# dababa.net
KiCad netlist of a schematic drawn in EAGLE
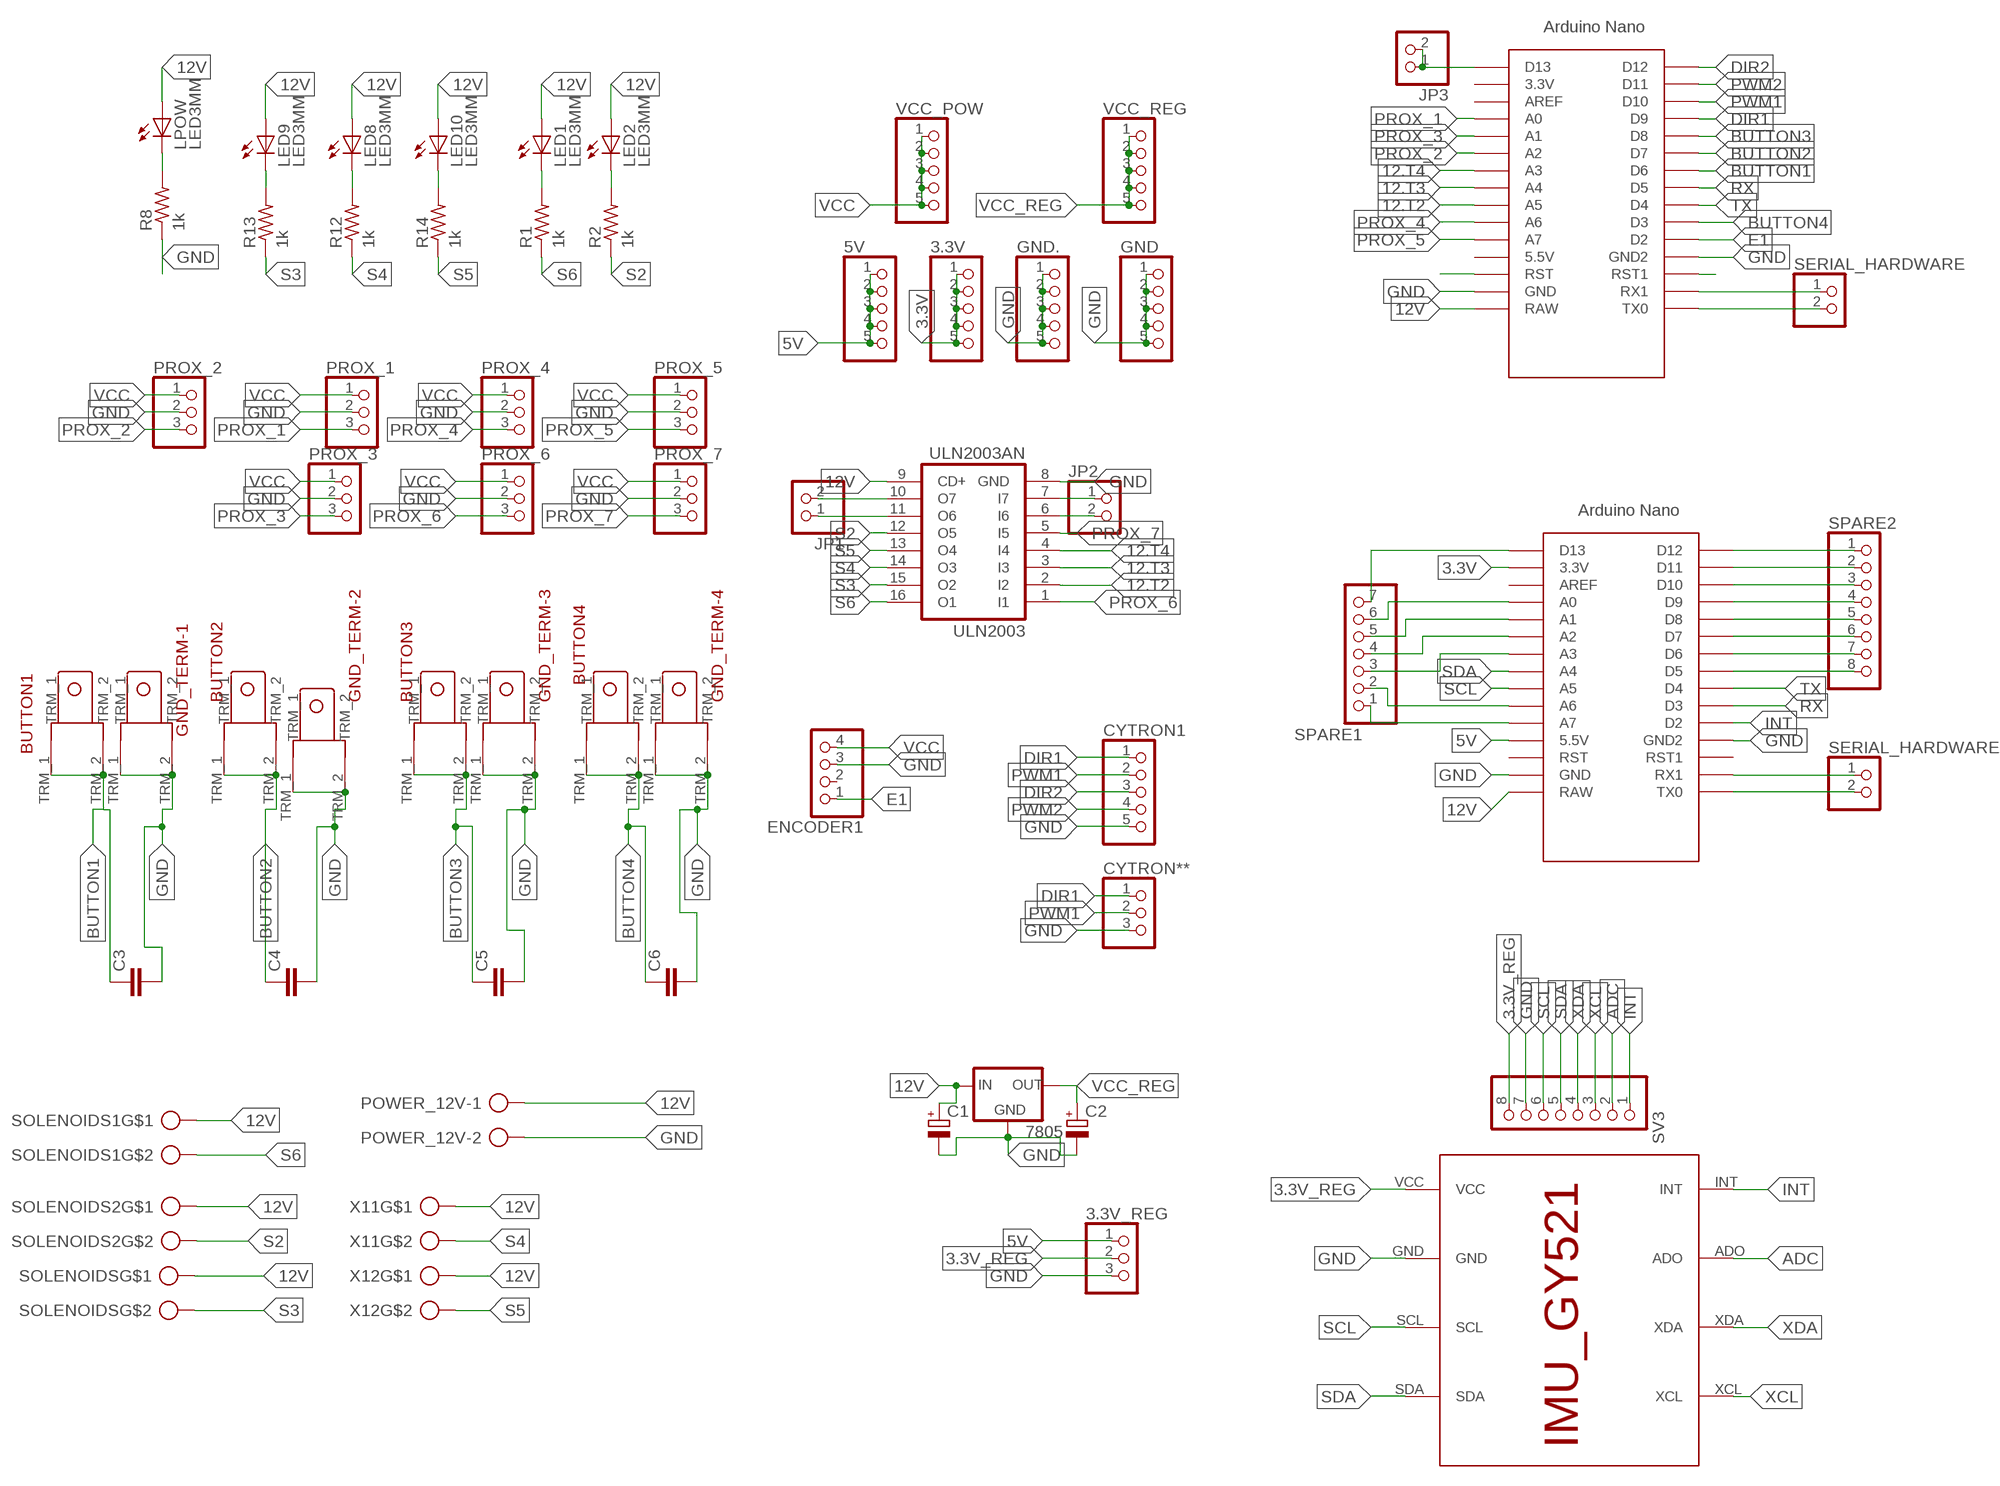
[diagram p0: schematic, sheet 1]

(export (version "E")
  (design (tool "Eeschema 10.0.6"))
  (components
    (comp (ref "3.3V")
      (value "PINHD-1X5")
      (footprint "eagle-import:1X05")
      (libsource (lib "eagle-import") (part "PINHD-1X5"))
    )
    (comp (ref "3.3V_REG")
      (value "PINHD-1X3")
      (footprint "eagle-import:1X03")
      (libsource (lib "eagle-import") (part "PINHD-1X3"))
    )
    (comp (ref "5V")
      (value "PINHD-1X5")
      (footprint "eagle-import:1X05")
      (libsource (lib "eagle-import") (part "PINHD-1X5"))
    )
    (comp (ref "7805")
      (value "78XXS")
      (footprint "eagle-import:78XXS")
      (libsource (lib "eagle-import") (part "78XXS"))
    )
    (comp (ref "BUTTON1")
      (value "TERMINAL_EDITED")
      (footprint "eagle-import:TERMINAL_EDITED")
      (libsource (lib "eagle-import") (part "TERMINAL_EDITED"))
    )
    (comp (ref "BUTTON2")
      (value "TERMINAL_EDITED")
      (footprint "eagle-import:TERMINAL_EDITED")
      (libsource (lib "eagle-import") (part "TERMINAL_EDITED"))
    )
    (comp (ref "BUTTON3")
      (value "TERMINAL_EDITED")
      (footprint "eagle-import:TERMINAL_EDITED")
      (libsource (lib "eagle-import") (part "TERMINAL_EDITED"))
    )
    (comp (ref "BUTTON4")
      (value "TERMINAL_EDITED")
      (footprint "eagle-import:TERMINAL_EDITED")
      (libsource (lib "eagle-import") (part "TERMINAL_EDITED"))
    )
    (comp (ref "C1")
      (value "CAP_POL")
      (footprint "eagle-import:E3,5-8")
      (libsource (lib "eagle-import") (part "CAP_POL"))
    )
    (comp (ref "C2")
      (value "CAP_POL")
      (footprint "eagle-import:E3,5-8")
      (libsource (lib "eagle-import") (part "CAP_POL"))
    )
    (comp (ref "C3")
      (value "CAPACITOR")
      (footprint "eagle-import:C025-025X050")
      (libsource (lib "eagle-import") (part "CAPACITOR"))
    )
    (comp (ref "C4")
      (value "CAPACITOR")
      (footprint "eagle-import:C025-025X050")
      (libsource (lib "eagle-import") (part "CAPACITOR"))
    )
    (comp (ref "C5")
      (value "CAPACITOR")
      (footprint "eagle-import:C025-025X050")
      (libsource (lib "eagle-import") (part "CAPACITOR"))
    )
    (comp (ref "C6")
      (value "CAPACITOR")
      (footprint "eagle-import:C025-025X050")
      (libsource (lib "eagle-import") (part "CAPACITOR"))
    )
    (comp (ref "CYTRON**")
      (value "PINHD-1X3")
      (footprint "eagle-import:1X03")
      (libsource (lib "eagle-import") (part "PINHD-1X3"))
    )
    (comp (ref "CYTRON1")
      (value "PINHD-1X5")
      (footprint "eagle-import:1X05")
      (libsource (lib "eagle-import") (part "PINHD-1X5"))
    )
    (comp (ref "ENCODER1")
      (value "PINHD-1X4")
      (footprint "eagle-import:1X04")
      (libsource (lib "eagle-import") (part "PINHD-1X4"))
    )
    (comp (ref "GND")
      (value "PINHD-1X5")
      (footprint "eagle-import:1X05")
      (libsource (lib "eagle-import") (part "PINHD-1X5"))
    )
    (comp (ref "GND.")
      (value "PINHD-1X5")
      (footprint "eagle-import:1X05")
      (libsource (lib "eagle-import") (part "PINHD-1X5"))
    )
    (comp (ref "GND_TERM-1")
      (value "TERMINAL_EDITED")
      (footprint "eagle-import:TERMINAL_EDITED")
      (libsource (lib "eagle-import") (part "TERMINAL_EDITED"))
    )
    (comp (ref "GND_TERM-2")
      (value "TERMINAL_EDITED")
      (footprint "eagle-import:TERMINAL_EDITED")
      (libsource (lib "eagle-import") (part "TERMINAL_EDITED"))
    )
    (comp (ref "GND_TERM-3")
      (value "TERMINAL_EDITED")
      (footprint "eagle-import:TERMINAL_EDITED")
      (libsource (lib "eagle-import") (part "TERMINAL_EDITED"))
    )
    (comp (ref "GND_TERM-4")
      (value "TERMINAL_EDITED")
      (footprint "eagle-import:TERMINAL_EDITED")
      (libsource (lib "eagle-import") (part "TERMINAL_EDITED"))
    )
    (comp (ref "JP1")
      (value "PINHD-1X2")
      (footprint "eagle-import:1X02")
      (libsource (lib "eagle-import") (part "PINHD-1X2"))
    )
    (comp (ref "JP2")
      (value "PINHD-1X2")
      (footprint "eagle-import:1X02")
      (libsource (lib "eagle-import") (part "PINHD-1X2"))
    )
    (comp (ref "JP3")
      (value "PINHD-1X2")
      (footprint "eagle-import:1X02")
      (libsource (lib "eagle-import") (part "PINHD-1X2"))
    )
    (comp (ref "LED1")
      (value "LED3MM")
      (footprint "eagle-import:LED3MM")
      (libsource (lib "eagle-import") (part "LED3MM"))
    )
    (comp (ref "LED2")
      (value "LED3MM")
      (footprint "eagle-import:LED3MM")
      (libsource (lib "eagle-import") (part "LED3MM"))
    )
    (comp (ref "LED8")
      (value "LED3MM")
      (footprint "eagle-import:LED3MM")
      (libsource (lib "eagle-import") (part "LED3MM"))
    )
    (comp (ref "LED9")
      (value "LED3MM")
      (footprint "eagle-import:LED3MM")
      (libsource (lib "eagle-import") (part "LED3MM"))
    )
    (comp (ref "LED10")
      (value "LED3MM")
      (footprint "eagle-import:LED3MM")
      (libsource (lib "eagle-import") (part "LED3MM"))
    )
    (comp (ref "LPOW")
      (value "LED3MM")
      (footprint "eagle-import:LED3MM")
      (libsource (lib "eagle-import") (part "LED3MM"))
    )
    (comp (ref "POWER_12V")
      (value "ROSTA.POWER")
      (footprint "eagle-import:W239-302")
      (libsource (lib "eagle-import") (part "ROSTA.POWER"))
    )
    (comp (ref "PROX_1")
      (value "PINHD-1X3")
      (footprint "eagle-import:1X03")
      (libsource (lib "eagle-import") (part "PINHD-1X3"))
    )
    (comp (ref "PROX_2")
      (value "PINHD-1X3")
      (footprint "eagle-import:1X03")
      (libsource (lib "eagle-import") (part "PINHD-1X3"))
    )
    (comp (ref "PROX_3")
      (value "PINHD-1X3")
      (footprint "eagle-import:1X03")
      (libsource (lib "eagle-import") (part "PINHD-1X3"))
    )
    (comp (ref "PROX_4")
      (value "PINHD-1X3")
      (footprint "eagle-import:1X03")
      (libsource (lib "eagle-import") (part "PINHD-1X3"))
    )
    (comp (ref "PROX_5")
      (value "PINHD-1X3")
      (footprint "eagle-import:1X03")
      (libsource (lib "eagle-import") (part "PINHD-1X3"))
    )
    (comp (ref "PROX_6")
      (value "PINHD-1X3")
      (footprint "eagle-import:1X03")
      (libsource (lib "eagle-import") (part "PINHD-1X3"))
    )
    (comp (ref "PROX_7")
      (value "PINHD-1X3")
      (footprint "eagle-import:1X03")
      (libsource (lib "eagle-import") (part "PINHD-1X3"))
    )
    (comp (ref "R1")
      (value "1k")
      (footprint "eagle-import:0204_5")
      (libsource (lib "eagle-import") (part "RES-5"))
    )
    (comp (ref "R2")
      (value "1k")
      (footprint "eagle-import:0204_5")
      (libsource (lib "eagle-import") (part "RES-5"))
    )
    (comp (ref "R8")
      (value "1k")
      (footprint "eagle-import:0204_5")
      (libsource (lib "eagle-import") (part "RES-5"))
    )
    (comp (ref "R12")
      (value "1k")
      (footprint "eagle-import:0204_5")
      (libsource (lib "eagle-import") (part "RES-5"))
    )
    (comp (ref "R13")
      (value "1k")
      (footprint "eagle-import:0204_5")
      (libsource (lib "eagle-import") (part "RES-5"))
    )
    (comp (ref "R14")
      (value "1k")
      (footprint "eagle-import:0204_5")
      (libsource (lib "eagle-import") (part "RES-5"))
    )
    (comp (ref "SERIAL_HARDWARE")
      (value "PINHD-1X2")
      (footprint "eagle-import:1X02")
      (libsource (lib "eagle-import") (part "PINHD-1X2"))
    )
    (comp (ref "SERIAL_HARDWARE1")
      (value "PINHD-1X2")
      (footprint "eagle-import:1X02")
      (libsource (lib "eagle-import") (part "PINHD-1X2"))
    )
    (comp (ref "SOLENOIDS")
      (value "CON_PTR_2")
      (footprint "eagle-import:AK300_2")
      (libsource (lib "eagle-import") (part "CON_PTR_2"))
    )
    (comp (ref "SOLENOIDS1")
      (value "CON_PTR_2")
      (footprint "eagle-import:AK300_2")
      (libsource (lib "eagle-import") (part "CON_PTR_2"))
    )
    (comp (ref "SOLENOIDS2")
      (value "CON_PTR_2")
      (footprint "eagle-import:AK300_2")
      (libsource (lib "eagle-import") (part "CON_PTR_2"))
    )
    (comp (ref "SPARE1")
      (value "PINHD-1X7")
      (footprint "eagle-import:1X07")
      (libsource (lib "eagle-import") (part "PINHD-1X7"))
    )
    (comp (ref "SPARE2")
      (value "PINHD-1X8")
      (footprint "eagle-import:1X08")
      (libsource (lib "eagle-import") (part "PINHD-1X8"))
    )
    (comp (ref "SV3")
      (value "PINHD-1X8")
      (footprint "eagle-import:1X08")
      (libsource (lib "eagle-import") (part "PINHD-1X8"))
    )
    (comp (ref "U$1")
      (value "ARDUINO_NANO")
      (footprint "eagle-import:NANO")
      (libsource (lib "eagle-import") (part "ARDUINO_NANO"))
    )
    (comp (ref "U$2")
      (value "IMU_ROBOCON_GY521")
      (footprint "eagle-import:IMU_GY521")
      (libsource (lib "eagle-import") (part "IMU_ROBOCON_GY521"))
    )
    (comp (ref "U$4")
      (value "ARDUINO_NANO")
      (footprint "eagle-import:NANO")
      (libsource (lib "eagle-import") (part "ARDUINO_NANO"))
    )
    (comp (ref "ULN2003")
      (value "ULN2003AN")
      (footprint "eagle-import:DIL16")
      (libsource (lib "eagle-import") (part "ULN2003AN"))
    )
    (comp (ref "VCC_POW")
      (value "PINHD-1X5")
      (footprint "eagle-import:1X05")
      (libsource (lib "eagle-import") (part "PINHD-1X5"))
    )
    (comp (ref "VCC_REG")
      (value "PINHD-1X5")
      (footprint "eagle-import:1X05")
      (libsource (lib "eagle-import") (part "PINHD-1X5"))
    )
    (comp (ref "X11")
      (value "CON_PTR_2")
      (footprint "eagle-import:AK300_2")
      (libsource (lib "eagle-import") (part "CON_PTR_2"))
    )
    (comp (ref "X12")
      (value "CON_PTR_2")
      (footprint "eagle-import:AK300_2")
      (libsource (lib "eagle-import") (part "CON_PTR_2"))
    )
  )
  (nets
    (net (code "1") (name "3.3V") (class "Default")
      (node (ref "3.3V") (pin "1") (pinfunction "1_1") (pintype "passive"))
      (node (ref "3.3V") (pin "2") (pinfunction "2_2") (pintype "passive"))
      (node (ref "3.3V") (pin "3") (pinfunction "3_3") (pintype "passive"))
      (node (ref "3.3V") (pin "4") (pinfunction "4_4") (pintype "passive"))
      (node (ref "3.3V") (pin "5") (pinfunction "5_5") (pintype "passive"))
      (node (ref "U$4") (pin "3.3V") (pinfunction "3.3V_3.3V") (pintype "bidirectional"))
    )
    (net (code "2") (name "3.3V_REG") (class "Default")
      (node (ref "3.3V_REG") (pin "2") (pinfunction "2_2") (pintype "passive"))
      (node (ref "SV3") (pin "8") (pinfunction "8_8") (pintype "passive"))
      (node (ref "U$2") (pin "VCC") (pinfunction "VCC_VCC") (pintype "bidirectional"))
    )
    (net (code "3") (name "5V") (class "Default")
      (node (ref "3.3V_REG") (pin "1") (pinfunction "1_1") (pintype "passive"))
      (node (ref "5V") (pin "1") (pinfunction "1_1") (pintype "passive"))
      (node (ref "5V") (pin "2") (pinfunction "2_2") (pintype "passive"))
      (node (ref "5V") (pin "3") (pinfunction "3_3") (pintype "passive"))
      (node (ref "5V") (pin "4") (pinfunction "4_4") (pintype "passive"))
      (node (ref "5V") (pin "5") (pinfunction "5_5") (pintype "passive"))
      (node (ref "U$4") (pin "5V") (pinfunction "5.5V_5V") (pintype "bidirectional"))
    )
    (net (code "4") (name "12.T2") (class "Default")
      (node (ref "U$1") (pin "A5") (pinfunction "A5_A5") (pintype "bidirectional"))
      (node (ref "ULN2003") (pin "2") (pinfunction "I2_2") (pintype "input"))
    )
    (net (code "5") (name "12.T3") (class "Default")
      (node (ref "U$1") (pin "A4") (pinfunction "A4_A4") (pintype "bidirectional"))
      (node (ref "ULN2003") (pin "3") (pinfunction "I3_3") (pintype "input"))
    )
    (net (code "6") (name "12.T4") (class "Default")
      (node (ref "U$1") (pin "A3") (pinfunction "A3_A3") (pintype "bidirectional"))
      (node (ref "ULN2003") (pin "4") (pinfunction "I4_4") (pintype "input"))
    )
    (net (code "7") (name "12V") (class "Default")
      (node (ref "7805") (pin "IN") (pinfunction "IN_IN") (pintype "input"))
      (node (ref "C1") (pin "+") (pinfunction "+_+") (pintype "passive"))
      (node (ref "LED1") (pin "A") (pinfunction "A_A") (pintype "passive"))
      (node (ref "LED10") (pin "A") (pinfunction "A_A") (pintype "passive"))
      (node (ref "LED2") (pin "A") (pinfunction "A_A") (pintype "passive"))
      (node (ref "LED8") (pin "A") (pinfunction "A_A") (pintype "passive"))
      (node (ref "LED9") (pin "A") (pinfunction "A_A") (pintype "passive"))
      (node (ref "LPOW") (pin "A") (pinfunction "A_A") (pintype "passive"))
      (node (ref "POWER_12V") (pin "1") (pinfunction "KL_1") (pintype "passive"))
      (node (ref "SOLENOIDS") (pin "1") (pinfunction "KL_1") (pintype "passive"))
      (node (ref "SOLENOIDS1") (pin "1") (pinfunction "KL_1") (pintype "passive"))
      (node (ref "SOLENOIDS2") (pin "1") (pinfunction "KL_1") (pintype "passive"))
      (node (ref "U$1") (pin "RAW") (pinfunction "RAW_RAW") (pintype "bidirectional"))
      (node (ref "U$4") (pin "RAW") (pinfunction "RAW_RAW") (pintype "bidirectional"))
      (node (ref "ULN2003") (pin "9") (pinfunction "CD+_9") (pintype "passive"))
      (node (ref "X11") (pin "1") (pinfunction "KL_1") (pintype "passive"))
      (node (ref "X12") (pin "1") (pinfunction "KL_1") (pintype "passive"))
    )
    (net (code "8") (name "ADC") (class "Default")
      (node (ref "SV3") (pin "2") (pinfunction "2_2") (pintype "passive"))
      (node (ref "U$2") (pin "ADO") (pinfunction "ADO_ADO") (pintype "bidirectional"))
    )
    (net (code "9") (name "BUTTON1") (class "Default")
      (node (ref "BUTTON1") (pin "TRM_1") (pinfunction "TRM_1_TRM_1") (pintype "bidirectional"))
      (node (ref "BUTTON1") (pin "TRM_2") (pinfunction "TRM_2_TRM_2") (pintype "bidirectional"))
      (node (ref "C3") (pin "1") (pinfunction "1_1") (pintype "passive"))
      (node (ref "U$1") (pin "D6") (pinfunction "D6_D6") (pintype "bidirectional"))
    )
    (net (code "10") (name "BUTTON2") (class "Default")
      (node (ref "BUTTON2") (pin "TRM_1") (pinfunction "TRM_1_TRM_1") (pintype "bidirectional"))
      (node (ref "BUTTON2") (pin "TRM_2") (pinfunction "TRM_2_TRM_2") (pintype "bidirectional"))
      (node (ref "C4") (pin "1") (pinfunction "1_1") (pintype "passive"))
      (node (ref "U$1") (pin "D7") (pinfunction "D7_D7") (pintype "bidirectional"))
    )
    (net (code "11") (name "BUTTON3") (class "Default")
      (node (ref "BUTTON3") (pin "TRM_1") (pinfunction "TRM_1_TRM_1") (pintype "bidirectional"))
      (node (ref "BUTTON3") (pin "TRM_2") (pinfunction "TRM_2_TRM_2") (pintype "bidirectional"))
      (node (ref "C5") (pin "1") (pinfunction "1_1") (pintype "passive"))
      (node (ref "U$1") (pin "D8") (pinfunction "D8_D8") (pintype "bidirectional"))
    )
    (net (code "12") (name "BUTTON4") (class "Default")
      (node (ref "BUTTON4") (pin "TRM_1") (pinfunction "TRM_1_TRM_1") (pintype "bidirectional"))
      (node (ref "BUTTON4") (pin "TRM_2") (pinfunction "TRM_2_TRM_2") (pintype "bidirectional"))
      (node (ref "C6") (pin "1") (pinfunction "1_1") (pintype "passive"))
      (node (ref "U$1") (pin "D3") (pinfunction "D3_D3") (pintype "bidirectional"))
    )
    (net (code "13") (name "DIR1") (class "Default")
      (node (ref "CYTRON**") (pin "1") (pinfunction "1_1") (pintype "passive"))
      (node (ref "CYTRON1") (pin "1") (pinfunction "1_1") (pintype "passive"))
      (node (ref "U$1") (pin "D9") (pinfunction "D9_D9") (pintype "bidirectional"))
    )
    (net (code "14") (name "DIR2") (class "Default")
      (node (ref "CYTRON1") (pin "3") (pinfunction "3_3") (pintype "passive"))
      (node (ref "U$1") (pin "D12") (pinfunction "D12_D12") (pintype "bidirectional"))
    )
    (net (code "15") (name "E1") (class "Default")
      (node (ref "ENCODER1") (pin "1") (pinfunction "1_1") (pintype "passive"))
      (node (ref "U$1") (pin "D2") (pinfunction "D2_D2") (pintype "bidirectional"))
    )
    (net (code "16") (name "GND") (class "Default")
      (node (ref "3.3V_REG") (pin "3") (pinfunction "3_3") (pintype "passive"))
      (node (ref "7805") (pin "GND") (pinfunction "GND_GND") (pintype "input"))
      (node (ref "C1") (pin "-") (pinfunction "-_-") (pintype "passive"))
      (node (ref "C2") (pin "-") (pinfunction "-_-") (pintype "passive"))
      (node (ref "C3") (pin "2") (pinfunction "2_2") (pintype "passive"))
      (node (ref "C4") (pin "2") (pinfunction "2_2") (pintype "passive"))
      (node (ref "C5") (pin "2") (pinfunction "2_2") (pintype "passive"))
      (node (ref "C6") (pin "2") (pinfunction "2_2") (pintype "passive"))
      (node (ref "CYTRON**") (pin "3") (pinfunction "3_3") (pintype "passive"))
      (node (ref "CYTRON1") (pin "5") (pinfunction "5_5") (pintype "passive"))
      (node (ref "ENCODER1") (pin "3") (pinfunction "3_3") (pintype "passive"))
      (node (ref "GND") (pin "1") (pinfunction "1_1") (pintype "passive"))
      (node (ref "GND") (pin "2") (pinfunction "2_2") (pintype "passive"))
      (node (ref "GND") (pin "3") (pinfunction "3_3") (pintype "passive"))
      (node (ref "GND") (pin "4") (pinfunction "4_4") (pintype "passive"))
      (node (ref "GND") (pin "5") (pinfunction "5_5") (pintype "passive"))
      (node (ref "GND.") (pin "1") (pinfunction "1_1") (pintype "passive"))
      (node (ref "GND.") (pin "2") (pinfunction "2_2") (pintype "passive"))
      (node (ref "GND.") (pin "3") (pinfunction "3_3") (pintype "passive"))
      (node (ref "GND.") (pin "4") (pinfunction "4_4") (pintype "passive"))
      (node (ref "GND.") (pin "5") (pinfunction "5_5") (pintype "passive"))
      (node (ref "GND_TERM-1") (pin "TRM_1") (pinfunction "TRM_1_TRM_1") (pintype "bidirectional"))
      (node (ref "GND_TERM-1") (pin "TRM_2") (pinfunction "TRM_2_TRM_2") (pintype "bidirectional"))
      (node (ref "GND_TERM-2") (pin "TRM_1") (pinfunction "TRM_1_TRM_1") (pintype "bidirectional"))
      (node (ref "GND_TERM-2") (pin "TRM_2") (pinfunction "TRM_2_TRM_2") (pintype "bidirectional"))
      (node (ref "GND_TERM-3") (pin "TRM_1") (pinfunction "TRM_1_TRM_1") (pintype "bidirectional"))
      (node (ref "GND_TERM-3") (pin "TRM_2") (pinfunction "TRM_2_TRM_2") (pintype "bidirectional"))
      (node (ref "GND_TERM-4") (pin "TRM_1") (pinfunction "TRM_1_TRM_1") (pintype "bidirectional"))
      (node (ref "GND_TERM-4") (pin "TRM_2") (pinfunction "TRM_2_TRM_2") (pintype "bidirectional"))
      (node (ref "POWER_12V") (pin "2") (pinfunction "KL_2") (pintype "passive"))
      (node (ref "PROX_1") (pin "2") (pinfunction "2_2") (pintype "passive"))
      (node (ref "PROX_2") (pin "2") (pinfunction "2_2") (pintype "passive"))
      (node (ref "PROX_3") (pin "2") (pinfunction "2_2") (pintype "passive"))
      (node (ref "PROX_4") (pin "2") (pinfunction "2_2") (pintype "passive"))
      (node (ref "PROX_5") (pin "2") (pinfunction "2_2") (pintype "passive"))
      (node (ref "PROX_6") (pin "2") (pinfunction "2_2") (pintype "passive"))
      (node (ref "PROX_7") (pin "2") (pinfunction "2_2") (pintype "passive"))
      (node (ref "R8") (pin "1") (pinfunction "1_1") (pintype "passive"))
      (node (ref "SV3") (pin "7") (pinfunction "7_7") (pintype "passive"))
      (node (ref "U$1") (pin "GND") (pinfunction "GND_GND") (pintype "bidirectional"))
      (node (ref "U$1") (pin "GND1") (pinfunction "GND2_GND1") (pintype "bidirectional"))
      (node (ref "U$2") (pin "GND") (pinfunction "GND_GND") (pintype "bidirectional"))
      (node (ref "U$4") (pin "GND") (pinfunction "GND_GND") (pintype "bidirectional"))
      (node (ref "U$4") (pin "GND1") (pinfunction "GND2_GND1") (pintype "bidirectional"))
      (node (ref "ULN2003") (pin "8") (pinfunction "GND_8") (pintype "power_in"))
    )
    (net (code "17") (name "INT") (class "Default")
      (node (ref "SV3") (pin "1") (pinfunction "1_1") (pintype "passive"))
      (node (ref "U$2") (pin "INT") (pinfunction "INT_INT") (pintype "bidirectional"))
      (node (ref "U$4") (pin "D2") (pinfunction "D2_D2") (pintype "bidirectional"))
    )
    (net (code "18") (name "Net-(JP3-Pad1)") (class "Default")
      (node (ref "JP3") (pin "1") (pinfunction "1_1") (pintype "passive"))
      (node (ref "JP3") (pin "2") (pinfunction "2_2") (pintype "passive"))
      (node (ref "U$1") (pin "D13") (pinfunction "D13_D13") (pintype "bidirectional"))
    )
    (net (code "19") (name "Net-(LED1-C)") (class "Default")
      (node (ref "LED1") (pin "K") (pinfunction "C_K") (pintype "passive"))
      (node (ref "R1") (pin "2") (pinfunction "2_2") (pintype "passive"))
    )
    (net (code "20") (name "Net-(LED2-C)") (class "Default")
      (node (ref "LED2") (pin "K") (pinfunction "C_K") (pintype "passive"))
      (node (ref "R2") (pin "2") (pinfunction "2_2") (pintype "passive"))
    )
    (net (code "21") (name "Net-(LED8-C)") (class "Default")
      (node (ref "LED8") (pin "K") (pinfunction "C_K") (pintype "passive"))
      (node (ref "R12") (pin "2") (pinfunction "2_2") (pintype "passive"))
    )
    (net (code "22") (name "Net-(LED9-C)") (class "Default")
      (node (ref "LED9") (pin "K") (pinfunction "C_K") (pintype "passive"))
      (node (ref "R13") (pin "2") (pinfunction "2_2") (pintype "passive"))
    )
    (net (code "23") (name "Net-(LED10-C)") (class "Default")
      (node (ref "LED10") (pin "K") (pinfunction "C_K") (pintype "passive"))
      (node (ref "R14") (pin "2") (pinfunction "2_2") (pintype "passive"))
    )
    (net (code "24") (name "Net-(LPOW-C)") (class "Default")
      (node (ref "LPOW") (pin "K") (pinfunction "C_K") (pintype "passive"))
      (node (ref "R8") (pin "2") (pinfunction "2_2") (pintype "passive"))
    )
    (net (code "25") (name "Net-(SERIAL_HARDWARE-Pad1)") (class "Default")
      (node (ref "SERIAL_HARDWARE") (pin "1") (pinfunction "1_1") (pintype "passive"))
      (node (ref "U$1") (pin "RX1") (pinfunction "RX1_RX1") (pintype "bidirectional"))
    )
    (net (code "26") (name "Net-(SERIAL_HARDWARE-Pad2)") (class "Default")
      (node (ref "SERIAL_HARDWARE") (pin "2") (pinfunction "2_2") (pintype "passive"))
      (node (ref "U$1") (pin "TX0") (pinfunction "TX0_TX0") (pintype "bidirectional"))
    )
    (net (code "27") (name "Net-(SERIAL_HARDWARE1-Pad1)") (class "Default")
      (node (ref "SERIAL_HARDWARE1") (pin "1") (pinfunction "1_1") (pintype "passive"))
      (node (ref "U$4") (pin "RX1") (pinfunction "RX1_RX1") (pintype "bidirectional"))
    )
    (net (code "28") (name "Net-(SERIAL_HARDWARE1-Pad2)") (class "Default")
      (node (ref "SERIAL_HARDWARE1") (pin "2") (pinfunction "2_2") (pintype "passive"))
      (node (ref "U$4") (pin "TX0") (pinfunction "TX0_TX0") (pintype "bidirectional"))
    )
    (net (code "29") (name "Net-(SPARE1-Pad1)") (class "Default")
      (node (ref "SPARE1") (pin "1") (pinfunction "1_1") (pintype "passive"))
      (node (ref "U$4") (pin "A7") (pinfunction "A7_A7") (pintype "bidirectional"))
    )
    (net (code "30") (name "Net-(SPARE1-Pad2)") (class "Default")
      (node (ref "SPARE1") (pin "2") (pinfunction "2_2") (pintype "passive"))
      (node (ref "U$4") (pin "A6") (pinfunction "A6_A6") (pintype "bidirectional"))
    )
    (net (code "31") (name "Net-(SPARE1-Pad3)") (class "Default")
      (node (ref "SPARE1") (pin "3") (pinfunction "3_3") (pintype "passive"))
      (node (ref "U$4") (pin "A3") (pinfunction "A3_A3") (pintype "bidirectional"))
    )
    (net (code "32") (name "Net-(SPARE1-Pad4)") (class "Default")
      (node (ref "SPARE1") (pin "4") (pinfunction "4_4") (pintype "passive"))
      (node (ref "U$4") (pin "A2") (pinfunction "A2_A2") (pintype "bidirectional"))
    )
    (net (code "33") (name "Net-(SPARE1-Pad5)") (class "Default")
      (node (ref "SPARE1") (pin "5") (pinfunction "5_5") (pintype "passive"))
      (node (ref "U$4") (pin "A1") (pinfunction "A1_A1") (pintype "bidirectional"))
    )
    (net (code "34") (name "Net-(SPARE1-Pad6)") (class "Default")
      (node (ref "SPARE1") (pin "6") (pinfunction "6_6") (pintype "passive"))
      (node (ref "U$4") (pin "A0") (pinfunction "A0_A0") (pintype "bidirectional"))
    )
    (net (code "35") (name "Net-(SPARE1-Pad7)") (class "Default")
      (node (ref "SPARE1") (pin "7") (pinfunction "7_7") (pintype "passive"))
      (node (ref "U$4") (pin "D13") (pinfunction "D13_D13") (pintype "bidirectional"))
    )
    (net (code "36") (name "Net-(SPARE2-Pad1)") (class "Default")
      (node (ref "SPARE2") (pin "1") (pinfunction "1_1") (pintype "passive"))
      (node (ref "U$4") (pin "D12") (pinfunction "D12_D12") (pintype "bidirectional"))
    )
    (net (code "37") (name "Net-(SPARE2-Pad2)") (class "Default")
      (node (ref "SPARE2") (pin "2") (pinfunction "2_2") (pintype "passive"))
      (node (ref "U$4") (pin "D11") (pinfunction "D11_D11") (pintype "bidirectional"))
    )
    (net (code "38") (name "Net-(SPARE2-Pad3)") (class "Default")
      (node (ref "SPARE2") (pin "3") (pinfunction "3_3") (pintype "passive"))
      (node (ref "U$4") (pin "D10") (pinfunction "D10_D10") (pintype "bidirectional"))
    )
    (net (code "39") (name "Net-(SPARE2-Pad4)") (class "Default")
      (node (ref "SPARE2") (pin "4") (pinfunction "4_4") (pintype "passive"))
      (node (ref "U$4") (pin "D9") (pinfunction "D9_D9") (pintype "bidirectional"))
    )
    (net (code "40") (name "Net-(SPARE2-Pad5)") (class "Default")
      (node (ref "SPARE2") (pin "5") (pinfunction "5_5") (pintype "passive"))
      (node (ref "U$4") (pin "D8") (pinfunction "D8_D8") (pintype "bidirectional"))
    )
    (net (code "41") (name "Net-(SPARE2-Pad6)") (class "Default")
      (node (ref "SPARE2") (pin "6") (pinfunction "6_6") (pintype "passive"))
      (node (ref "U$4") (pin "D7") (pinfunction "D7_D7") (pintype "bidirectional"))
    )
    (net (code "42") (name "Net-(SPARE2-Pad7)") (class "Default")
      (node (ref "SPARE2") (pin "7") (pinfunction "7_7") (pintype "passive"))
      (node (ref "U$4") (pin "D6") (pinfunction "D6_D6") (pintype "bidirectional"))
    )
    (net (code "43") (name "Net-(SPARE2-Pad8)") (class "Default")
      (node (ref "SPARE2") (pin "8") (pinfunction "8_8") (pintype "passive"))
      (node (ref "U$4") (pin "D5") (pinfunction "D5_D5") (pintype "bidirectional"))
    )
    (net (code "44") (name "Net-(ULN2003-I6)") (class "Default")
      (node (ref "JP2") (pin "2") (pinfunction "2_2") (pintype "passive"))
      (node (ref "ULN2003") (pin "6") (pinfunction "I6_6") (pintype "input"))
    )
    (net (code "45") (name "Net-(ULN2003-I7)") (class "Default")
      (node (ref "JP2") (pin "1") (pinfunction "1_1") (pintype "passive"))
      (node (ref "ULN2003") (pin "7") (pinfunction "I7_7") (pintype "input"))
    )
    (net (code "46") (name "Net-(ULN2003-O6)") (class "Default")
      (node (ref "JP1") (pin "1") (pinfunction "1_1") (pintype "passive"))
      (node (ref "ULN2003") (pin "11") (pinfunction "O6_11") (pintype "open_collector"))
    )
    (net (code "47") (name "Net-(ULN2003-O7)") (class "Default")
      (node (ref "JP1") (pin "2") (pinfunction "2_2") (pintype "passive"))
      (node (ref "ULN2003") (pin "10") (pinfunction "O7_10") (pintype "open_collector"))
    )
    (net (code "48") (name "PROX_1") (class "Default")
      (node (ref "PROX_1") (pin "3") (pinfunction "3_3") (pintype "passive"))
      (node (ref "U$1") (pin "A0") (pinfunction "A0_A0") (pintype "bidirectional"))
    )
    (net (code "49") (name "PROX_2") (class "Default")
      (node (ref "PROX_2") (pin "3") (pinfunction "3_3") (pintype "passive"))
      (node (ref "U$1") (pin "A2") (pinfunction "A2_A2") (pintype "bidirectional"))
    )
    (net (code "50") (name "PROX_3") (class "Default")
      (node (ref "PROX_3") (pin "3") (pinfunction "3_3") (pintype "passive"))
      (node (ref "U$1") (pin "A1") (pinfunction "A1_A1") (pintype "bidirectional"))
    )
    (net (code "51") (name "PROX_4") (class "Default")
      (node (ref "PROX_4") (pin "3") (pinfunction "3_3") (pintype "passive"))
      (node (ref "U$1") (pin "A6") (pinfunction "A6_A6") (pintype "bidirectional"))
    )
    (net (code "52") (name "PROX_5") (class "Default")
      (node (ref "PROX_5") (pin "3") (pinfunction "3_3") (pintype "passive"))
      (node (ref "U$1") (pin "A7") (pinfunction "A7_A7") (pintype "bidirectional"))
    )
    (net (code "53") (name "PROX_6") (class "Default")
      (node (ref "PROX_6") (pin "3") (pinfunction "3_3") (pintype "passive"))
      (node (ref "ULN2003") (pin "1") (pinfunction "I1_1") (pintype "input"))
    )
    (net (code "54") (name "PROX_7") (class "Default")
      (node (ref "PROX_7") (pin "3") (pinfunction "3_3") (pintype "passive"))
      (node (ref "ULN2003") (pin "5") (pinfunction "I5_5") (pintype "input"))
    )
    (net (code "55") (name "PWM1") (class "Default")
      (node (ref "CYTRON**") (pin "2") (pinfunction "2_2") (pintype "passive"))
      (node (ref "CYTRON1") (pin "2") (pinfunction "2_2") (pintype "passive"))
      (node (ref "U$1") (pin "D10") (pinfunction "D10_D10") (pintype "bidirectional"))
    )
    (net (code "56") (name "PWM2") (class "Default")
      (node (ref "CYTRON1") (pin "4") (pinfunction "4_4") (pintype "passive"))
      (node (ref "U$1") (pin "D11") (pinfunction "D11_D11") (pintype "bidirectional"))
    )
    (net (code "57") (name "RX") (class "Default")
      (node (ref "U$1") (pin "D5") (pinfunction "D5_D5") (pintype "bidirectional"))
      (node (ref "U$4") (pin "D3") (pinfunction "D3_D3") (pintype "bidirectional"))
    )
    (net (code "58") (name "S2") (class "Default")
      (node (ref "R2") (pin "1") (pinfunction "1_1") (pintype "passive"))
      (node (ref "SOLENOIDS2") (pin "2") (pinfunction "KL_2") (pintype "passive"))
      (node (ref "ULN2003") (pin "12") (pinfunction "O5_12") (pintype "open_collector"))
    )
    (net (code "59") (name "S3") (class "Default")
      (node (ref "R13") (pin "1") (pinfunction "1_1") (pintype "passive"))
      (node (ref "SOLENOIDS") (pin "2") (pinfunction "KL_2") (pintype "passive"))
      (node (ref "ULN2003") (pin "15") (pinfunction "O2_15") (pintype "open_collector"))
    )
    (net (code "60") (name "S4") (class "Default")
      (node (ref "R12") (pin "1") (pinfunction "1_1") (pintype "passive"))
      (node (ref "ULN2003") (pin "14") (pinfunction "O3_14") (pintype "open_collector"))
      (node (ref "X11") (pin "2") (pinfunction "KL_2") (pintype "passive"))
    )
    (net (code "61") (name "S5") (class "Default")
      (node (ref "R14") (pin "1") (pinfunction "1_1") (pintype "passive"))
      (node (ref "ULN2003") (pin "13") (pinfunction "O4_13") (pintype "open_collector"))
      (node (ref "X12") (pin "2") (pinfunction "KL_2") (pintype "passive"))
    )
    (net (code "62") (name "S6") (class "Default")
      (node (ref "R1") (pin "1") (pinfunction "1_1") (pintype "passive"))
      (node (ref "SOLENOIDS1") (pin "2") (pinfunction "KL_2") (pintype "passive"))
      (node (ref "ULN2003") (pin "16") (pinfunction "O1_16") (pintype "open_collector"))
    )
    (net (code "63") (name "SCL") (class "Default")
      (node (ref "SV3") (pin "6") (pinfunction "6_6") (pintype "passive"))
      (node (ref "U$2") (pin "SCL") (pinfunction "SCL_SCL") (pintype "bidirectional"))
      (node (ref "U$4") (pin "A5") (pinfunction "A5_A5") (pintype "bidirectional"))
    )
    (net (code "64") (name "SDA") (class "Default")
      (node (ref "SV3") (pin "5") (pinfunction "5_5") (pintype "passive"))
      (node (ref "U$2") (pin "SDA") (pinfunction "SDA_SDA") (pintype "bidirectional"))
      (node (ref "U$4") (pin "A4") (pinfunction "A4_A4") (pintype "bidirectional"))
    )
    (net (code "65") (name "TX") (class "Default")
      (node (ref "U$1") (pin "D4") (pinfunction "D4_D4") (pintype "bidirectional"))
      (node (ref "U$4") (pin "D4") (pinfunction "D4_D4") (pintype "bidirectional"))
    )
    (net (code "66") (name "VCC") (class "Default")
      (node (ref "ENCODER1") (pin "4") (pinfunction "4_4") (pintype "passive"))
      (node (ref "PROX_1") (pin "1") (pinfunction "1_1") (pintype "passive"))
      (node (ref "PROX_2") (pin "1") (pinfunction "1_1") (pintype "passive"))
      (node (ref "PROX_3") (pin "1") (pinfunction "1_1") (pintype "passive"))
      (node (ref "PROX_4") (pin "1") (pinfunction "1_1") (pintype "passive"))
      (node (ref "PROX_5") (pin "1") (pinfunction "1_1") (pintype "passive"))
      (node (ref "PROX_6") (pin "1") (pinfunction "1_1") (pintype "passive"))
      (node (ref "PROX_7") (pin "1") (pinfunction "1_1") (pintype "passive"))
      (node (ref "VCC_POW") (pin "1") (pinfunction "1_1") (pintype "passive"))
      (node (ref "VCC_POW") (pin "2") (pinfunction "2_2") (pintype "passive"))
      (node (ref "VCC_POW") (pin "3") (pinfunction "3_3") (pintype "passive"))
      (node (ref "VCC_POW") (pin "4") (pinfunction "4_4") (pintype "passive"))
      (node (ref "VCC_POW") (pin "5") (pinfunction "5_5") (pintype "passive"))
    )
    (net (code "67") (name "VCC_REG") (class "Default")
      (node (ref "7805") (pin "OUT") (pinfunction "OUT_OUT") (pintype "passive"))
      (node (ref "C2") (pin "+") (pinfunction "+_+") (pintype "passive"))
      (node (ref "VCC_REG") (pin "1") (pinfunction "1_1") (pintype "passive"))
      (node (ref "VCC_REG") (pin "2") (pinfunction "2_2") (pintype "passive"))
      (node (ref "VCC_REG") (pin "3") (pinfunction "3_3") (pintype "passive"))
      (node (ref "VCC_REG") (pin "4") (pinfunction "4_4") (pintype "passive"))
      (node (ref "VCC_REG") (pin "5") (pinfunction "5_5") (pintype "passive"))
    )
    (net (code "68") (name "XCL") (class "Default")
      (node (ref "SV3") (pin "3") (pinfunction "3_3") (pintype "passive"))
      (node (ref "U$2") (pin "XCL") (pinfunction "XCL_XCL") (pintype "bidirectional"))
    )
    (net (code "69") (name "XDA") (class "Default")
      (node (ref "SV3") (pin "4") (pinfunction "4_4") (pintype "passive"))
      (node (ref "U$2") (pin "XDA") (pinfunction "XDA_XDA") (pintype "bidirectional"))
    )
    (net (code "70") (name "unconnected-(ENCODER1-Pad2)") (class "Default")
      (node (ref "ENCODER1") (pin "2") (pinfunction "2_2") (pintype "passive"))
    )
    (net (code "71") (name "unconnected-(U$1-5.5V-Pad5V)") (class "Default")
      (node (ref "U$1") (pin "5V") (pinfunction "5.5V_5V") (pintype "bidirectional"))
    )
    (net (code "72") (name "unconnected-(U$1-Pad3.3V)") (class "Default")
      (node (ref "U$1") (pin "3.3V") (pinfunction "3.3V_3.3V") (pintype "bidirectional"))
    )
    (net (code "73") (name "unconnected-(U$1-PadAREF)") (class "Default")
      (node (ref "U$1") (pin "AREF") (pinfunction "AREF_AREF") (pintype "bidirectional"))
    )
    (net (code "74") (name "unconnected-(U$1-PadRST)") (class "Default")
      (node (ref "U$1") (pin "RST") (pinfunction "RST_RST") (pintype "bidirectional"))
    )
    (net (code "75") (name "unconnected-(U$1-PadRST1)") (class "Default")
      (node (ref "U$1") (pin "RST1") (pinfunction "RST1_RST1") (pintype "bidirectional"))
    )
    (net (code "76") (name "unconnected-(U$4-PadAREF)") (class "Default")
      (node (ref "U$4") (pin "AREF") (pinfunction "AREF_AREF") (pintype "bidirectional"))
    )
    (net (code "77") (name "unconnected-(U$4-PadRST)") (class "Default")
      (node (ref "U$4") (pin "RST") (pinfunction "RST_RST") (pintype "bidirectional"))
    )
    (net (code "78") (name "unconnected-(U$4-PadRST1)") (class "Default")
      (node (ref "U$4") (pin "RST1") (pinfunction "RST1_RST1") (pintype "bidirectional"))
    )
  )
)
